# RS485_Shield_Max13487.net
KiCad netlist of a schematic drawn in EAGLE
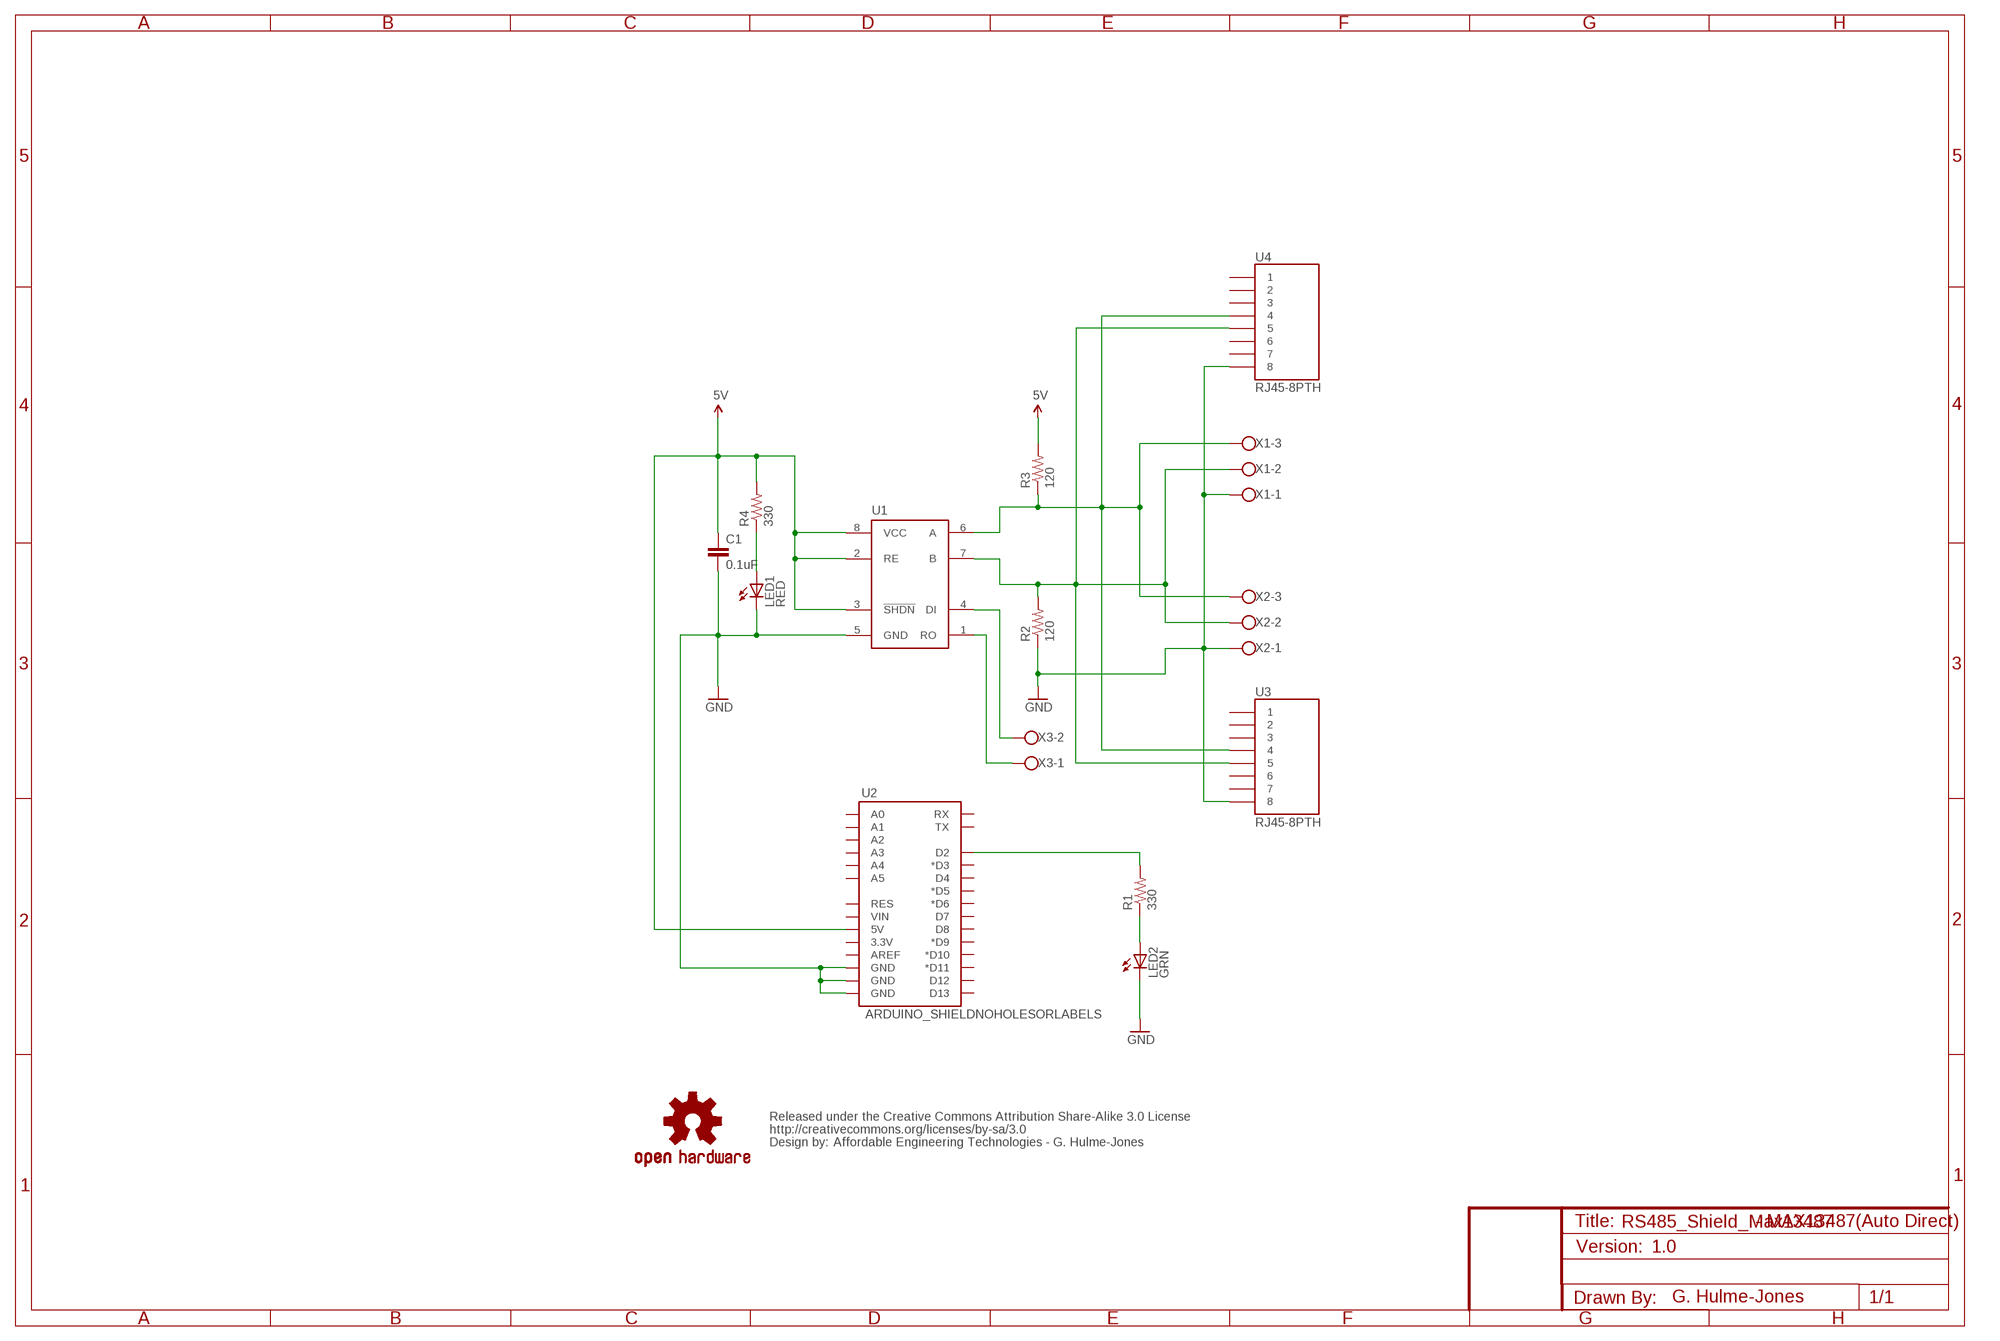
[diagram p0: schematic, sheet 1]

(export (version "E")
  (design (tool "Eeschema 10.0.6"))
  (components
    (comp (ref "C1")
      (value "0.1uF")
      (footprint "eagle-import:0402-CAP")
      (libsource (lib "eagle-import") (part "CAP0402-CAP"))
    )
    (comp (ref "CC_TEXT1")
      (value "CREATIVE_COMMONS")
      (footprint "eagle-import:CREATIVE_COMMONS")
      (libsource (lib "eagle-import") (part "CREATIVE_COMMONS"))
    )
    (comp (ref "LED1")
      (value "RED")
      (footprint "eagle-import:LED-0603")
      (libsource (lib "eagle-import") (part "LED0603"))
    )
    (comp (ref "LED2")
      (value "GRN")
      (footprint "eagle-import:LED-0603")
      (libsource (lib "eagle-import") (part "LED0603"))
    )
    (comp (ref "LOGO1")
      (value "OSHW-LOGOL")
      (footprint "eagle-import:OSHW-LOGO-L")
      (libsource (lib "eagle-import") (part "OSHW-LOGOL"))
    )
    (comp (ref "R1")
      (value "330")
      (footprint "eagle-import:0402-RES")
      (libsource (lib "eagle-import") (part "RESISTOR0402-RES"))
    )
    (comp (ref "R2")
      (value "120")
      (footprint "eagle-import:0402-RES")
      (libsource (lib "eagle-import") (part "RESISTOR0402-RES"))
    )
    (comp (ref "R3")
      (value "120")
      (footprint "eagle-import:0402-RES")
      (libsource (lib "eagle-import") (part "RESISTOR0402-RES"))
    )
    (comp (ref "R4")
      (value "330")
      (footprint "eagle-import:0402-RES")
      (libsource (lib "eagle-import") (part "RESISTOR0402-RES"))
    )
    (comp (ref "U1")
      (value "MAX13487")
      (footprint "eagle-import:MAX13487")
      (libsource (lib "eagle-import") (part "MAX13487SOIC"))
    )
    (comp (ref "U2")
      (value "ARDUINO_SHIELDNOHOLESORLABELS")
      (footprint "eagle-import:DUEMILANOVE_SHIELD_NOHOLES_NOLABELS")
      (libsource (lib "eagle-import") (part "ARDUINO_SHIELDNOHOLESORLABELS"))
    )
    (comp (ref "U3")
      (value "RJ45-8PTH")
      (footprint "eagle-import:RJ45-8")
      (libsource (lib "eagle-import") (part "RJ45-8PTH"))
    )
    (comp (ref "U4")
      (value "RJ45-8PTH")
      (footprint "eagle-import:RJ45-8")
      (libsource (lib "eagle-import") (part "RJ45-8PTH"))
    )
    (comp (ref "X1")
      (value "W237-103")
      (footprint "eagle-import:W237-103")
      (fields (field (name "MPN") "237-103"))
      (libsource (lib "eagle-import") (part "W237-103"))
    )
    (comp (ref "X2")
      (value "W237-103")
      (footprint "eagle-import:W237-103")
      (fields (field (name "MPN") "237-103"))
      (libsource (lib "eagle-import") (part "W237-103"))
    )
    (comp (ref "X3")
      (value "W237-102")
      (footprint "eagle-import:W237-102")
      (fields (field (name "MPN") "237-102"))
      (libsource (lib "eagle-import") (part "W237-102"))
    )
  )
  (nets
    (net (code "1") (name "5V") (class "Default")
      (node (ref "C1") (pin "1") (pinfunction "1_1") (pintype "passive"))
      (node (ref "R3") (pin "2") (pinfunction "2_2") (pintype "passive"))
      (node (ref "R4") (pin "2") (pinfunction "2_2") (pintype "passive"))
      (node (ref "U1") (pin "2") (pinfunction "RE_2") (pintype "bidirectional"))
      (node (ref "U1") (pin "3") (pinfunction "~{SHDN}_3") (pintype "bidirectional"))
      (node (ref "U1") (pin "8") (pinfunction "VCC_8") (pintype "power_in"))
      (node (ref "U2") (pin "5V") (pinfunction "5V_5V") (pintype "bidirectional"))
    )
    (net (code "2") (name "GND") (class "Default")
      (node (ref "C1") (pin "2") (pinfunction "2_2") (pintype "passive"))
      (node (ref "LED1") (pin "C") (pinfunction "C_C") (pintype "passive"))
      (node (ref "LED2") (pin "C") (pinfunction "C_C") (pintype "passive"))
      (node (ref "R2") (pin "1") (pinfunction "1_1") (pintype "passive"))
      (node (ref "U1") (pin "5") (pinfunction "GND_5") (pintype "power_in"))
      (node (ref "U2") (pin "GND@0") (pinfunction "GND_GND@0") (pintype "bidirectional"))
      (node (ref "U2") (pin "GND@1") (pinfunction "GND_GND@1") (pintype "bidirectional"))
      (node (ref "U2") (pin "GND@2") (pinfunction "GND_GND@2") (pintype "bidirectional"))
      (node (ref "U3") (pin "8") (pinfunction "8_8") (pintype "bidirectional"))
      (node (ref "U4") (pin "8") (pinfunction "8_8") (pintype "bidirectional"))
      (node (ref "X1") (pin "1") (pinfunction "KL_1") (pintype "passive"))
      (node (ref "X2") (pin "1") (pinfunction "KL_1") (pintype "passive"))
    )
    (net (code "3") (name "Net-(LED1-PadA)") (class "Default")
      (node (ref "LED1") (pin "A") (pinfunction "A_A") (pintype "passive"))
      (node (ref "R4") (pin "1") (pinfunction "1_1") (pintype "passive"))
    )
    (net (code "4") (name "Net-(LED2-PadA)") (class "Default")
      (node (ref "LED2") (pin "A") (pinfunction "A_A") (pintype "passive"))
      (node (ref "R1") (pin "1") (pinfunction "1_1") (pintype "passive"))
    )
    (net (code "5") (name "Net-(R1-Pad2)") (class "Default")
      (node (ref "R1") (pin "2") (pinfunction "2_2") (pintype "passive"))
      (node (ref "U2") (pin "D2") (pinfunction "D2_D2") (pintype "bidirectional"))
    )
    (net (code "6") (name "Net-(U1-A)") (class "Default")
      (node (ref "R3") (pin "1") (pinfunction "1_1") (pintype "passive"))
      (node (ref "U1") (pin "6") (pinfunction "A_6") (pintype "bidirectional"))
      (node (ref "U3") (pin "4") (pinfunction "4_4") (pintype "bidirectional"))
      (node (ref "U4") (pin "4") (pinfunction "4_4") (pintype "bidirectional"))
      (node (ref "X1") (pin "3") (pinfunction "KL_3") (pintype "passive"))
      (node (ref "X2") (pin "3") (pinfunction "KL_3") (pintype "passive"))
    )
    (net (code "7") (name "Net-(U1-B)") (class "Default")
      (node (ref "R2") (pin "2") (pinfunction "2_2") (pintype "passive"))
      (node (ref "U1") (pin "7") (pinfunction "B_7") (pintype "bidirectional"))
      (node (ref "U3") (pin "5") (pinfunction "5_5") (pintype "bidirectional"))
      (node (ref "U4") (pin "5") (pinfunction "5_5") (pintype "bidirectional"))
      (node (ref "X1") (pin "2") (pinfunction "KL_2") (pintype "passive"))
      (node (ref "X2") (pin "2") (pinfunction "KL_2") (pintype "passive"))
    )
    (net (code "8") (name "Net-(U1-DI)") (class "Default")
      (node (ref "U1") (pin "4") (pinfunction "DI_4") (pintype "input"))
      (node (ref "X3") (pin "2") (pinfunction "KL_2") (pintype "passive"))
    )
    (net (code "9") (name "Net-(U1-RO)") (class "Default")
      (node (ref "U1") (pin "1") (pinfunction "RO_1") (pintype "output"))
      (node (ref "X3") (pin "1") (pinfunction "KL_1") (pintype "passive"))
    )
    (net (code "10") (name "unconnected-(U2-*D3-PadD3)") (class "Default")
      (node (ref "U2") (pin "D3") (pinfunction "*D3_D3") (pintype "bidirectional"))
    )
    (net (code "11") (name "unconnected-(U2-*D5-PadD5)") (class "Default")
      (node (ref "U2") (pin "D5") (pinfunction "*D5_D5") (pintype "bidirectional"))
    )
    (net (code "12") (name "unconnected-(U2-*D6-PadD6)") (class "Default")
      (node (ref "U2") (pin "D6") (pinfunction "*D6_D6") (pintype "bidirectional"))
    )
    (net (code "13") (name "unconnected-(U2-*D9-PadD9)") (class "Default")
      (node (ref "U2") (pin "D9") (pinfunction "*D9_D9") (pintype "bidirectional"))
    )
    (net (code "14") (name "unconnected-(U2-*D10-PadD10)") (class "Default")
      (node (ref "U2") (pin "D10") (pinfunction "*D10_D10") (pintype "bidirectional"))
    )
    (net (code "15") (name "unconnected-(U2-*D11-PadD11)") (class "Default")
      (node (ref "U2") (pin "D11") (pinfunction "*D11_D11") (pintype "bidirectional"))
    )
    (net (code "16") (name "unconnected-(U2-Pad3.3V)") (class "Default")
      (node (ref "U2") (pin "3.3V") (pinfunction "3.3V_3.3V") (pintype "bidirectional"))
    )
    (net (code "17") (name "unconnected-(U2-PadA0)") (class "Default")
      (node (ref "U2") (pin "A0") (pinfunction "A0_A0") (pintype "bidirectional"))
    )
    (net (code "18") (name "unconnected-(U2-PadA1)") (class "Default")
      (node (ref "U2") (pin "A1") (pinfunction "A1_A1") (pintype "bidirectional"))
    )
    (net (code "19") (name "unconnected-(U2-PadA2)") (class "Default")
      (node (ref "U2") (pin "A2") (pinfunction "A2_A2") (pintype "bidirectional"))
    )
    (net (code "20") (name "unconnected-(U2-PadA3)") (class "Default")
      (node (ref "U2") (pin "A3") (pinfunction "A3_A3") (pintype "bidirectional"))
    )
    (net (code "21") (name "unconnected-(U2-PadA4)") (class "Default")
      (node (ref "U2") (pin "A4") (pinfunction "A4_A4") (pintype "bidirectional"))
    )
    (net (code "22") (name "unconnected-(U2-PadA5)") (class "Default")
      (node (ref "U2") (pin "A5") (pinfunction "A5_A5") (pintype "bidirectional"))
    )
    (net (code "23") (name "unconnected-(U2-PadAREF)") (class "Default")
      (node (ref "U2") (pin "AREF") (pinfunction "AREF_AREF") (pintype "bidirectional"))
    )
    (net (code "24") (name "unconnected-(U2-PadD4)") (class "Default")
      (node (ref "U2") (pin "D4") (pinfunction "D4_D4") (pintype "bidirectional"))
    )
    (net (code "25") (name "unconnected-(U2-PadD7)") (class "Default")
      (node (ref "U2") (pin "D7") (pinfunction "D7_D7") (pintype "bidirectional"))
    )
    (net (code "26") (name "unconnected-(U2-PadD8)") (class "Default")
      (node (ref "U2") (pin "D8") (pinfunction "D8_D8") (pintype "bidirectional"))
    )
    (net (code "27") (name "unconnected-(U2-PadD12)") (class "Default")
      (node (ref "U2") (pin "D12") (pinfunction "D12_D12") (pintype "bidirectional"))
    )
    (net (code "28") (name "unconnected-(U2-PadD13)") (class "Default")
      (node (ref "U2") (pin "D13") (pinfunction "D13_D13") (pintype "bidirectional"))
    )
    (net (code "29") (name "unconnected-(U2-PadRES)") (class "Default")
      (node (ref "U2") (pin "RES") (pinfunction "RES_RES") (pintype "bidirectional"))
    )
    (net (code "30") (name "unconnected-(U2-PadRX)") (class "Default")
      (node (ref "U2") (pin "RX") (pinfunction "RX_RX") (pintype "bidirectional"))
    )
    (net (code "31") (name "unconnected-(U2-PadTX)") (class "Default")
      (node (ref "U2") (pin "TX") (pinfunction "TX_TX") (pintype "bidirectional"))
    )
    (net (code "32") (name "unconnected-(U2-PadVIN)") (class "Default")
      (node (ref "U2") (pin "VIN") (pinfunction "VIN_VIN") (pintype "bidirectional"))
    )
    (net (code "33") (name "unconnected-(U3-Pad1)") (class "Default")
      (node (ref "U3") (pin "1") (pinfunction "1_1") (pintype "bidirectional"))
    )
    (net (code "34") (name "unconnected-(U3-Pad2)") (class "Default")
      (node (ref "U3") (pin "2") (pinfunction "2_2") (pintype "bidirectional"))
    )
    (net (code "35") (name "unconnected-(U3-Pad3)") (class "Default")
      (node (ref "U3") (pin "3") (pinfunction "3_3") (pintype "bidirectional"))
    )
    (net (code "36") (name "unconnected-(U3-Pad6)") (class "Default")
      (node (ref "U3") (pin "6") (pinfunction "6_6") (pintype "bidirectional"))
    )
    (net (code "37") (name "unconnected-(U3-Pad7)") (class "Default")
      (node (ref "U3") (pin "7") (pinfunction "7_7") (pintype "bidirectional"))
    )
    (net (code "38") (name "unconnected-(U4-Pad1)") (class "Default")
      (node (ref "U4") (pin "1") (pinfunction "1_1") (pintype "bidirectional"))
    )
    (net (code "39") (name "unconnected-(U4-Pad2)") (class "Default")
      (node (ref "U4") (pin "2") (pinfunction "2_2") (pintype "bidirectional"))
    )
    (net (code "40") (name "unconnected-(U4-Pad3)") (class "Default")
      (node (ref "U4") (pin "3") (pinfunction "3_3") (pintype "bidirectional"))
    )
    (net (code "41") (name "unconnected-(U4-Pad6)") (class "Default")
      (node (ref "U4") (pin "6") (pinfunction "6_6") (pintype "bidirectional"))
    )
    (net (code "42") (name "unconnected-(U4-Pad7)") (class "Default")
      (node (ref "U4") (pin "7") (pinfunction "7_7") (pintype "bidirectional"))
    )
  )
)
